# motor-driver.net
KiCad netlist of a schematic drawn in EAGLE
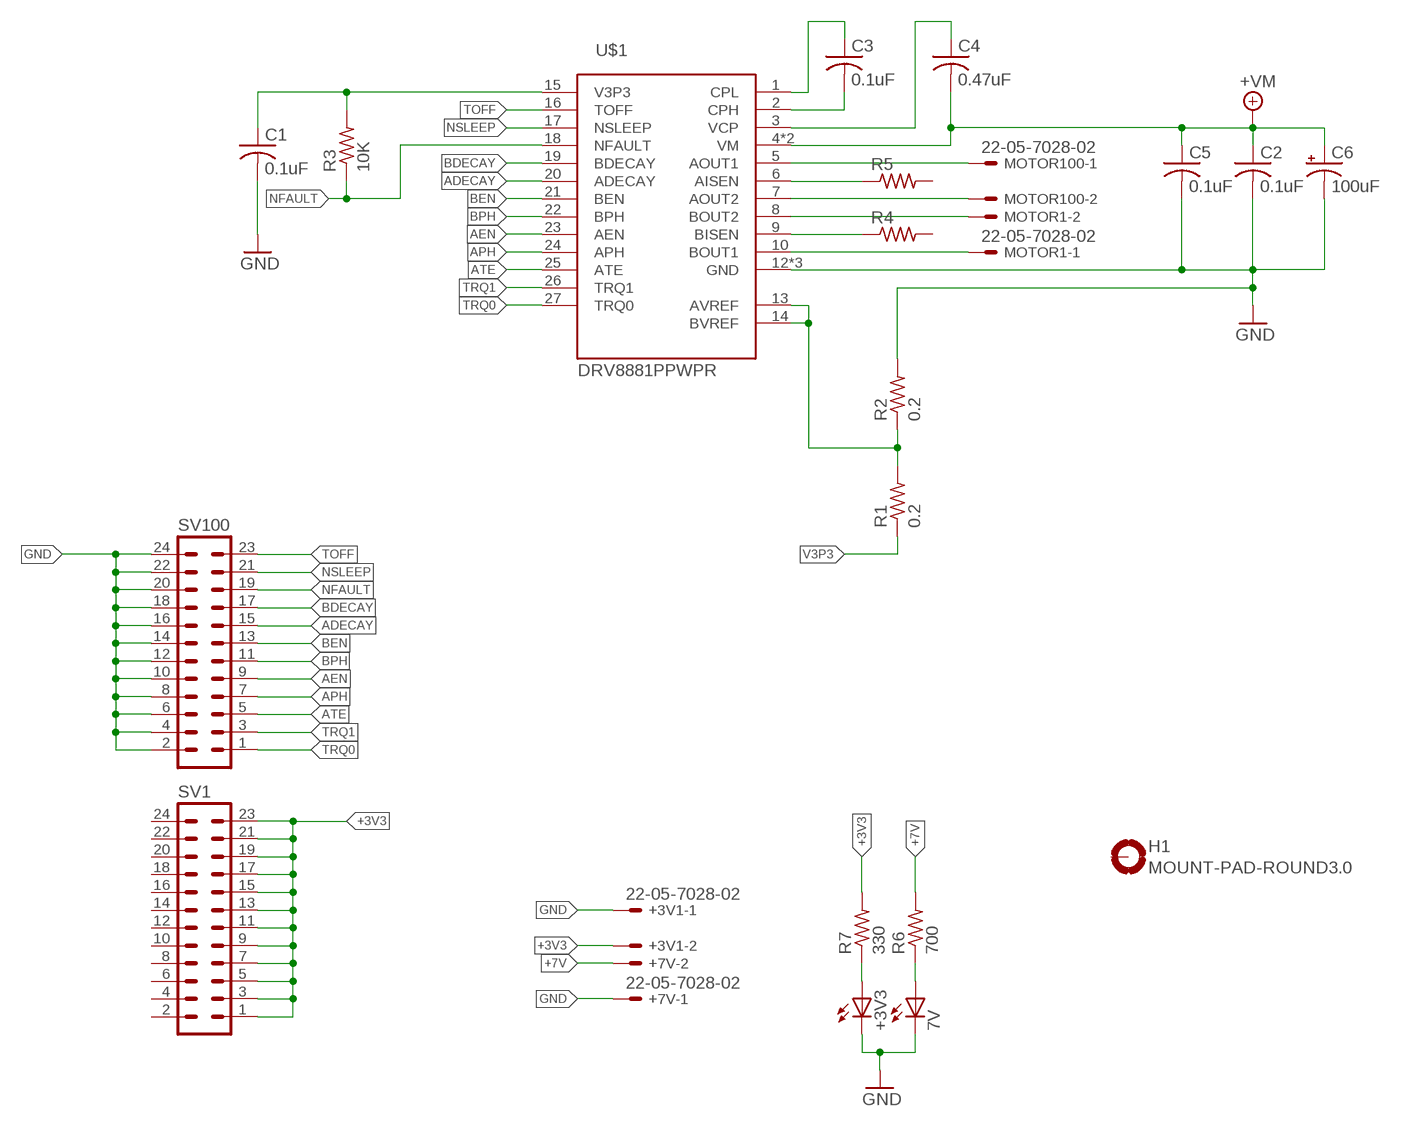
[diagram p0: schematic, sheet 1]

(export (version "E")
  (design (tool "Eeschema 10.0.6"))
  (components
    (comp (ref "+3V1")
      (value "22-05-7028-02")
      (footprint "eagle-import:7395-02")
      (libsource (lib "eagle-import") (part "22-?-0205-7028"))
    )
    (comp (ref "+3V3")
      (value "LEDCHIP-LED0603")
      (footprint "eagle-import:CHIP-LED0603")
      (libsource (lib "eagle-import") (part "LEDCHIP-LED0603"))
    )
    (comp (ref "+7V")
      (value "22-05-7028-02")
      (footprint "eagle-import:7395-02")
      (libsource (lib "eagle-import") (part "22-?-0205-7028"))
    )
    (comp (ref "7V")
      (value "LEDCHIP-LED0603")
      (footprint "eagle-import:CHIP-LED0603")
      (libsource (lib "eagle-import") (part "LEDCHIP-LED0603"))
    )
    (comp (ref "C1")
      (value "0.1uF")
      (footprint "eagle-import:C0402")
      (libsource (lib "eagle-import") (part "C-USC0402"))
    )
    (comp (ref "C2")
      (value "0.1uF")
      (footprint "eagle-import:C0402")
      (libsource (lib "eagle-import") (part "C-USC0402"))
    )
    (comp (ref "C3")
      (value "0.1uF")
      (footprint "eagle-import:C0402")
      (libsource (lib "eagle-import") (part "C-USC0402"))
    )
    (comp (ref "C4")
      (value "0.47uF")
      (footprint "eagle-import:C0402")
      (libsource (lib "eagle-import") (part "C-USC0402"))
    )
    (comp (ref "C5")
      (value "0.1uF")
      (footprint "eagle-import:C0402")
      (libsource (lib "eagle-import") (part "C-USC0402"))
    )
    (comp (ref "C6")
      (value "100uF")
      (footprint "eagle-import:EIA7343")
      (libsource (lib "eagle-import") (part "100UF-10V-10%(TANT)"))
    )
    (comp (ref "H1")
      (value "MOUNT-PAD-ROUND3.0")
      (footprint "eagle-import:3,0-PAD")
      (libsource (lib "eagle-import") (part "MOUNT-PAD-ROUND3.0"))
    )
    (comp (ref "MOTOR1")
      (value "22-05-7028-02")
      (footprint "eagle-import:7395-02")
      (libsource (lib "eagle-import") (part "22-?-0205-7028"))
    )
    (comp (ref "MOTOR100")
      (value "22-05-7028-02")
      (footprint "eagle-import:7395-02")
      (libsource (lib "eagle-import") (part "22-?-0205-7028"))
    )
    (comp (ref "R1")
      (value "0.2")
      (footprint "eagle-import:R0402")
      (libsource (lib "eagle-import") (part "R-US_R0402"))
    )
    (comp (ref "R2")
      (value "0.2")
      (footprint "eagle-import:R0402")
      (libsource (lib "eagle-import") (part "R-US_R0402"))
    )
    (comp (ref "R3")
      (value "10K")
      (footprint "eagle-import:R1206")
      (libsource (lib "eagle-import") (part "R-US_R1206"))
    )
    (comp (ref "R4")
      (value "R-US_R1206")
      (footprint "eagle-import:R1206")
      (libsource (lib "eagle-import") (part "R-US_R1206"))
    )
    (comp (ref "R5")
      (value "R-US_R1206")
      (footprint "eagle-import:R1206")
      (libsource (lib "eagle-import") (part "R-US_R1206"))
    )
    (comp (ref "R6")
      (value "700")
      (footprint "eagle-import:R0402")
      (libsource (lib "eagle-import") (part "R-US_R0402"))
    )
    (comp (ref "R7")
      (value "330")
      (footprint "eagle-import:R0402")
      (libsource (lib "eagle-import") (part "R-US_R0402"))
    )
    (comp (ref "SV1")
      (value "MA12-2")
      (footprint "eagle-import:MA12-2")
      (libsource (lib "eagle-import") (part "MA12-2"))
    )
    (comp (ref "SV100")
      (value "MA12-2")
      (footprint "eagle-import:MA12-2")
      (libsource (lib "eagle-import") (part "MA12-2"))
    )
    (comp (ref "U$1")
      (value "DRV8881PPWPR")
      (footprint "eagle-import:TSSOP-28")
      (libsource (lib "eagle-import") (part "DRV8881PPWPR"))
    )
  )
  (nets
    (net (code "1") (name "+3V3") (class "Default")
      (node (ref "+3V1") (pin "2") (pinfunction "S_2") (pintype "passive"))
      (node (ref "R7") (pin "2") (pinfunction "2_2") (pintype "passive"))
      (node (ref "SV1") (pin "1") (pinfunction "1_1") (pintype "passive"))
      (node (ref "SV1") (pin "11") (pinfunction "11_11") (pintype "passive"))
      (node (ref "SV1") (pin "13") (pinfunction "13_13") (pintype "passive"))
      (node (ref "SV1") (pin "15") (pinfunction "15_15") (pintype "passive"))
      (node (ref "SV1") (pin "17") (pinfunction "17_17") (pintype "passive"))
      (node (ref "SV1") (pin "19") (pinfunction "19_19") (pintype "passive"))
      (node (ref "SV1") (pin "21") (pinfunction "21_21") (pintype "passive"))
      (node (ref "SV1") (pin "23") (pinfunction "23_23") (pintype "passive"))
      (node (ref "SV1") (pin "3") (pinfunction "3_3") (pintype "passive"))
      (node (ref "SV1") (pin "5") (pinfunction "5_5") (pintype "passive"))
      (node (ref "SV1") (pin "7") (pinfunction "7_7") (pintype "passive"))
      (node (ref "SV1") (pin "9") (pinfunction "9_9") (pintype "passive"))
    )
    (net (code "2") (name "+7V") (class "Default")
      (node (ref "+7V") (pin "2") (pinfunction "S_2") (pintype "passive"))
      (node (ref "C2") (pin "1") (pinfunction "1_1") (pintype "passive"))
      (node (ref "C4") (pin "2") (pinfunction "2_2") (pintype "passive"))
      (node (ref "C5") (pin "1") (pinfunction "1_1") (pintype "passive"))
      (node (ref "C6") (pin "A") (pinfunction "+_A") (pintype "passive"))
      (node (ref "R6") (pin "2") (pinfunction "2_2") (pintype "passive"))
      (node (ref "U$1") (pin "11") (pinfunction "VM_11") (pintype "bidirectional"))
      (node (ref "U$1") (pin "4") (pinfunction "VM_4") (pintype "bidirectional"))
    )
    (net (code "3") (name "ADECAY") (class "Default")
      (node (ref "SV100") (pin "15") (pinfunction "15_15") (pintype "passive"))
      (node (ref "U$1") (pin "20") (pinfunction "ADECAY_20") (pintype "bidirectional"))
    )
    (net (code "4") (name "AEN") (class "Default")
      (node (ref "SV100") (pin "9") (pinfunction "9_9") (pintype "passive"))
      (node (ref "U$1") (pin "23") (pinfunction "AEN_23") (pintype "bidirectional"))
    )
    (net (code "5") (name "APH") (class "Default")
      (node (ref "SV100") (pin "7") (pinfunction "7_7") (pintype "passive"))
      (node (ref "U$1") (pin "24") (pinfunction "APH_24") (pintype "bidirectional"))
    )
    (net (code "6") (name "ATE") (class "Default")
      (node (ref "SV100") (pin "5") (pinfunction "5_5") (pintype "passive"))
      (node (ref "U$1") (pin "25") (pinfunction "ATE_25") (pintype "bidirectional"))
    )
    (net (code "7") (name "BDECAY") (class "Default")
      (node (ref "SV100") (pin "17") (pinfunction "17_17") (pintype "passive"))
      (node (ref "U$1") (pin "19") (pinfunction "BDECAY_19") (pintype "bidirectional"))
    )
    (net (code "8") (name "BEN") (class "Default")
      (node (ref "SV100") (pin "13") (pinfunction "13_13") (pintype "passive"))
      (node (ref "U$1") (pin "21") (pinfunction "BEN_21") (pintype "bidirectional"))
    )
    (net (code "9") (name "BPH") (class "Default")
      (node (ref "SV100") (pin "11") (pinfunction "11_11") (pintype "passive"))
      (node (ref "U$1") (pin "22") (pinfunction "BPH_22") (pintype "bidirectional"))
    )
    (net (code "10") (name "GND") (class "Default")
      (node (ref "+3V1") (pin "1") (pinfunction "S_1") (pintype "passive"))
      (node (ref "+3V3") (pin "C") (pinfunction "C_C") (pintype "passive"))
      (node (ref "+7V") (pin "1") (pinfunction "S_1") (pintype "passive"))
      (node (ref "7V") (pin "C") (pinfunction "C_C") (pintype "passive"))
      (node (ref "C1") (pin "2") (pinfunction "2_2") (pintype "passive"))
      (node (ref "C2") (pin "2") (pinfunction "2_2") (pintype "passive"))
      (node (ref "C5") (pin "2") (pinfunction "2_2") (pintype "passive"))
      (node (ref "C6") (pin "C") (pinfunction "-_C") (pintype "passive"))
      (node (ref "R2") (pin "2") (pinfunction "2_2") (pintype "passive"))
      (node (ref "SV100") (pin "10") (pinfunction "10_10") (pintype "passive"))
      (node (ref "SV100") (pin "12") (pinfunction "12_12") (pintype "passive"))
      (node (ref "SV100") (pin "14") (pinfunction "14_14") (pintype "passive"))
      (node (ref "SV100") (pin "16") (pinfunction "16_16") (pintype "passive"))
      (node (ref "SV100") (pin "18") (pinfunction "18_18") (pintype "passive"))
      (node (ref "SV100") (pin "2") (pinfunction "2_2") (pintype "passive"))
      (node (ref "SV100") (pin "20") (pinfunction "20_20") (pintype "passive"))
      (node (ref "SV100") (pin "22") (pinfunction "22_22") (pintype "passive"))
      (node (ref "SV100") (pin "24") (pinfunction "24_24") (pintype "passive"))
      (node (ref "SV100") (pin "4") (pinfunction "4_4") (pintype "passive"))
      (node (ref "SV100") (pin "6") (pinfunction "6_6") (pintype "passive"))
      (node (ref "SV100") (pin "8") (pinfunction "8_8") (pintype "passive"))
      (node (ref "U$1") (pin "12") (pinfunction "GND_12") (pintype "bidirectional"))
      (node (ref "U$1") (pin "28") (pinfunction "GND_28") (pintype "bidirectional"))
      (node (ref "U$1") (pin "EXP") (pinfunction "GND_EXP") (pintype "bidirectional"))
    )
    (net (code "11") (name "NFAULT") (class "Default")
      (node (ref "R3") (pin "1") (pinfunction "1_1") (pintype "passive"))
      (node (ref "SV100") (pin "19") (pinfunction "19_19") (pintype "passive"))
      (node (ref "U$1") (pin "18") (pinfunction "NFAULT_18") (pintype "bidirectional"))
    )
    (net (code "12") (name "NSLEEP") (class "Default")
      (node (ref "SV100") (pin "21") (pinfunction "21_21") (pintype "passive"))
      (node (ref "U$1") (pin "17") (pinfunction "NSLEEP_17") (pintype "bidirectional"))
    )
    (net (code "13") (name "Net-(+3V3-PadA)") (class "Default")
      (node (ref "+3V3") (pin "A") (pinfunction "A_A") (pintype "passive"))
      (node (ref "R7") (pin "1") (pinfunction "1_1") (pintype "passive"))
    )
    (net (code "14") (name "Net-(7V-PadA)") (class "Default")
      (node (ref "7V") (pin "A") (pinfunction "A_A") (pintype "passive"))
      (node (ref "R6") (pin "1") (pinfunction "1_1") (pintype "passive"))
    )
    (net (code "15") (name "Net-(MOTOR1A-S)") (class "Default")
      (node (ref "MOTOR1") (pin "1") (pinfunction "S_1") (pintype "passive"))
      (node (ref "U$1") (pin "10") (pinfunction "BOUT1_10") (pintype "bidirectional"))
    )
    (net (code "16") (name "Net-(MOTOR1B-S)") (class "Default")
      (node (ref "MOTOR1") (pin "2") (pinfunction "S_2") (pintype "passive"))
      (node (ref "U$1") (pin "8") (pinfunction "BOUT2_8") (pintype "bidirectional"))
    )
    (net (code "17") (name "Net-(MOTOR100A-S)") (class "Default")
      (node (ref "MOTOR100") (pin "1") (pinfunction "S_1") (pintype "passive"))
      (node (ref "U$1") (pin "5") (pinfunction "AOUT1_5") (pintype "bidirectional"))
    )
    (net (code "18") (name "Net-(MOTOR100B-S)") (class "Default")
      (node (ref "MOTOR100") (pin "2") (pinfunction "S_2") (pintype "passive"))
      (node (ref "U$1") (pin "7") (pinfunction "AOUT2_7") (pintype "bidirectional"))
    )
    (net (code "19") (name "Net-(U$1-AISEN)") (class "Default")
      (node (ref "R5") (pin "1") (pinfunction "1_1") (pintype "passive"))
      (node (ref "U$1") (pin "6") (pinfunction "AISEN_6") (pintype "bidirectional"))
    )
    (net (code "20") (name "Net-(U$1-AVREF)") (class "Default")
      (node (ref "R1") (pin "2") (pinfunction "2_2") (pintype "passive"))
      (node (ref "R2") (pin "1") (pinfunction "1_1") (pintype "passive"))
      (node (ref "U$1") (pin "13") (pinfunction "AVREF_13") (pintype "bidirectional"))
      (node (ref "U$1") (pin "14") (pinfunction "BVREF_14") (pintype "bidirectional"))
    )
    (net (code "21") (name "Net-(U$1-BISEN)") (class "Default")
      (node (ref "R4") (pin "1") (pinfunction "1_1") (pintype "passive"))
      (node (ref "U$1") (pin "9") (pinfunction "BISEN_9") (pintype "bidirectional"))
    )
    (net (code "22") (name "Net-(U$1-CPH)") (class "Default")
      (node (ref "C3") (pin "2") (pinfunction "2_2") (pintype "passive"))
      (node (ref "U$1") (pin "2") (pinfunction "CPH_2") (pintype "bidirectional"))
    )
    (net (code "23") (name "Net-(U$1-CPL)") (class "Default")
      (node (ref "C3") (pin "1") (pinfunction "1_1") (pintype "passive"))
      (node (ref "U$1") (pin "1") (pinfunction "CPL_1") (pintype "bidirectional"))
    )
    (net (code "24") (name "Net-(U$1-VCP)") (class "Default")
      (node (ref "C4") (pin "1") (pinfunction "1_1") (pintype "passive"))
      (node (ref "U$1") (pin "3") (pinfunction "VCP_3") (pintype "bidirectional"))
    )
    (net (code "25") (name "TOFF") (class "Default")
      (node (ref "SV100") (pin "23") (pinfunction "23_23") (pintype "passive"))
      (node (ref "U$1") (pin "16") (pinfunction "TOFF_16") (pintype "bidirectional"))
    )
    (net (code "26") (name "TRQ0") (class "Default")
      (node (ref "SV100") (pin "1") (pinfunction "1_1") (pintype "passive"))
      (node (ref "U$1") (pin "27") (pinfunction "TRQ0_27") (pintype "bidirectional"))
    )
    (net (code "27") (name "TRQ1") (class "Default")
      (node (ref "SV100") (pin "3") (pinfunction "3_3") (pintype "passive"))
      (node (ref "U$1") (pin "26") (pinfunction "TRQ1_26") (pintype "bidirectional"))
    )
    (net (code "28") (name "V3P3") (class "Default")
      (node (ref "C1") (pin "1") (pinfunction "1_1") (pintype "passive"))
      (node (ref "R1") (pin "1") (pinfunction "1_1") (pintype "passive"))
      (node (ref "R3") (pin "2") (pinfunction "2_2") (pintype "passive"))
      (node (ref "U$1") (pin "15") (pinfunction "V3P3_15") (pintype "bidirectional"))
    )
    (net (code "29") (name "unconnected-(H1-MOUNT-PadB3,0)") (class "Default")
      (node (ref "H1") (pin "B3,0") (pinfunction "MOUNT_B3,0") (pintype "passive"))
    )
    (net (code "30") (name "unconnected-(R4-Pad2)") (class "Default")
      (node (ref "R4") (pin "2") (pinfunction "2_2") (pintype "passive"))
    )
    (net (code "31") (name "unconnected-(R5-Pad2)") (class "Default")
      (node (ref "R5") (pin "2") (pinfunction "2_2") (pintype "passive"))
    )
    (net (code "32") (name "unconnected-(SV1-Pad2)") (class "Default")
      (node (ref "SV1") (pin "2") (pinfunction "2_2") (pintype "passive"))
    )
    (net (code "33") (name "unconnected-(SV1-Pad4)") (class "Default")
      (node (ref "SV1") (pin "4") (pinfunction "4_4") (pintype "passive"))
    )
    (net (code "34") (name "unconnected-(SV1-Pad6)") (class "Default")
      (node (ref "SV1") (pin "6") (pinfunction "6_6") (pintype "passive"))
    )
    (net (code "35") (name "unconnected-(SV1-Pad8)") (class "Default")
      (node (ref "SV1") (pin "8") (pinfunction "8_8") (pintype "passive"))
    )
    (net (code "36") (name "unconnected-(SV1-Pad10)") (class "Default")
      (node (ref "SV1") (pin "10") (pinfunction "10_10") (pintype "passive"))
    )
    (net (code "37") (name "unconnected-(SV1-Pad12)") (class "Default")
      (node (ref "SV1") (pin "12") (pinfunction "12_12") (pintype "passive"))
    )
    (net (code "38") (name "unconnected-(SV1-Pad14)") (class "Default")
      (node (ref "SV1") (pin "14") (pinfunction "14_14") (pintype "passive"))
    )
    (net (code "39") (name "unconnected-(SV1-Pad16)") (class "Default")
      (node (ref "SV1") (pin "16") (pinfunction "16_16") (pintype "passive"))
    )
    (net (code "40") (name "unconnected-(SV1-Pad18)") (class "Default")
      (node (ref "SV1") (pin "18") (pinfunction "18_18") (pintype "passive"))
    )
    (net (code "41") (name "unconnected-(SV1-Pad20)") (class "Default")
      (node (ref "SV1") (pin "20") (pinfunction "20_20") (pintype "passive"))
    )
    (net (code "42") (name "unconnected-(SV1-Pad22)") (class "Default")
      (node (ref "SV1") (pin "22") (pinfunction "22_22") (pintype "passive"))
    )
    (net (code "43") (name "unconnected-(SV1-Pad24)") (class "Default")
      (node (ref "SV1") (pin "24") (pinfunction "24_24") (pintype "passive"))
    )
  )
)
